# Visualizer_Bar.net
KiCad netlist of a schematic drawn in EAGLE
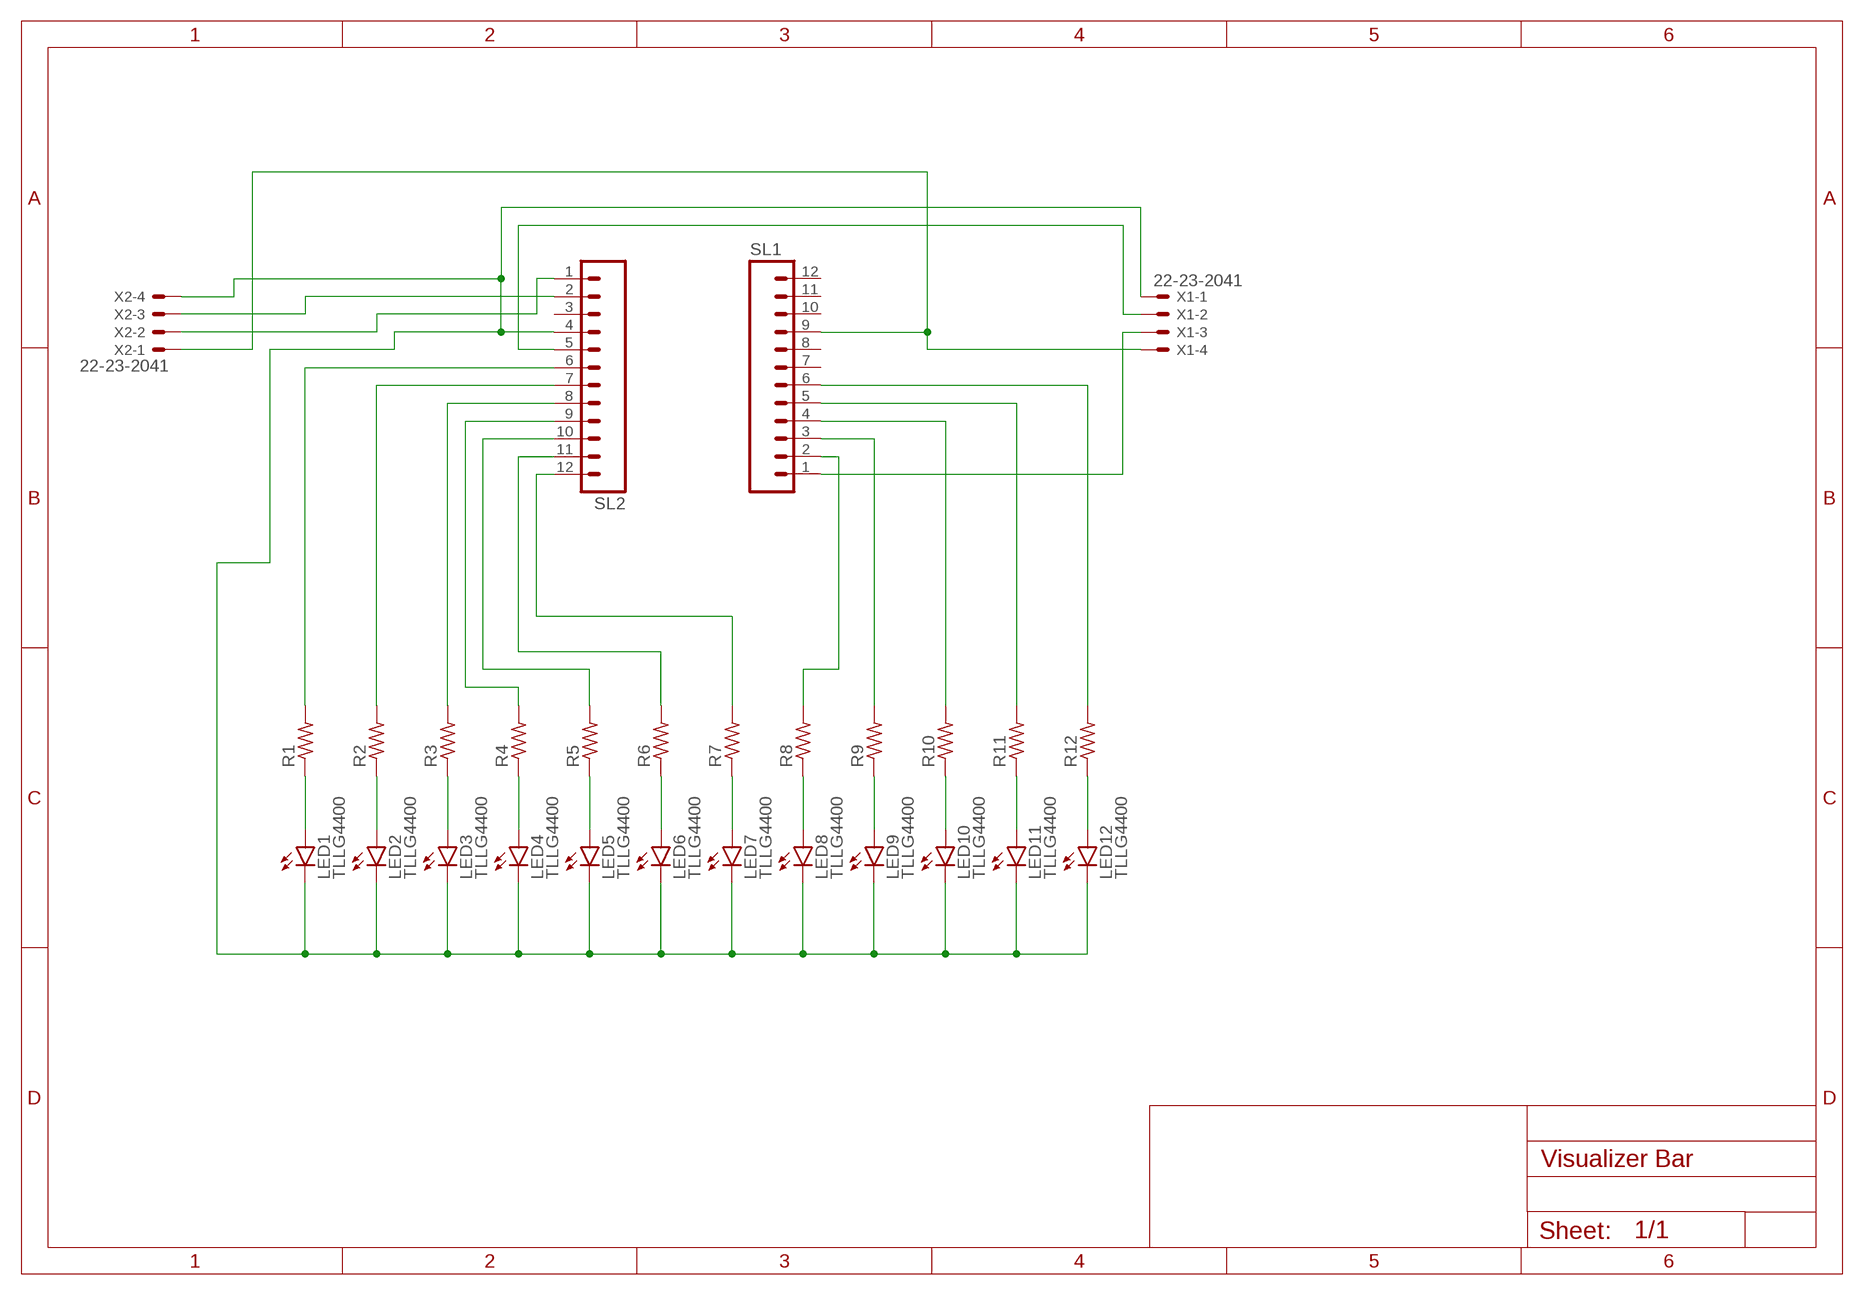
[diagram p0: schematic, sheet 1]

(export (version "E")
  (design (tool "Eeschema 10.0.6"))
  (components
    (comp (ref "LED1")
      (value "TLLG4400")
      (footprint "eagle-import:LED3MM")
      (fields (field (name "MF") "VISHAY SEMICONDUCTOR"))
      (libsource (lib "eagle-import") (part "TLLG4400"))
    )
    (comp (ref "LED2")
      (value "TLLG4400")
      (footprint "eagle-import:LED3MM")
      (fields (field (name "MF") "VISHAY SEMICONDUCTOR"))
      (libsource (lib "eagle-import") (part "TLLG4400"))
    )
    (comp (ref "LED3")
      (value "TLLG4400")
      (footprint "eagle-import:LED3MM")
      (fields (field (name "MF") "VISHAY SEMICONDUCTOR"))
      (libsource (lib "eagle-import") (part "TLLG4400"))
    )
    (comp (ref "LED4")
      (value "TLLG4400")
      (footprint "eagle-import:LED3MM")
      (fields (field (name "MF") "VISHAY SEMICONDUCTOR"))
      (libsource (lib "eagle-import") (part "TLLG4400"))
    )
    (comp (ref "LED5")
      (value "TLLG4400")
      (footprint "eagle-import:LED3MM")
      (fields (field (name "MF") "VISHAY SEMICONDUCTOR"))
      (libsource (lib "eagle-import") (part "TLLG4400"))
    )
    (comp (ref "LED6")
      (value "TLLG4400")
      (footprint "eagle-import:LED3MM")
      (fields (field (name "MF") "VISHAY SEMICONDUCTOR"))
      (libsource (lib "eagle-import") (part "TLLG4400"))
    )
    (comp (ref "LED7")
      (value "TLLG4400")
      (footprint "eagle-import:LED3MM")
      (fields (field (name "MF") "VISHAY SEMICONDUCTOR"))
      (libsource (lib "eagle-import") (part "TLLG4400"))
    )
    (comp (ref "LED8")
      (value "TLLG4400")
      (footprint "eagle-import:LED3MM")
      (fields (field (name "MF") "VISHAY SEMICONDUCTOR"))
      (libsource (lib "eagle-import") (part "TLLG4400"))
    )
    (comp (ref "LED9")
      (value "TLLG4400")
      (footprint "eagle-import:LED3MM")
      (fields (field (name "MF") "VISHAY SEMICONDUCTOR"))
      (libsource (lib "eagle-import") (part "TLLG4400"))
    )
    (comp (ref "LED10")
      (value "TLLG4400")
      (footprint "eagle-import:LED3MM")
      (fields (field (name "MF") "VISHAY SEMICONDUCTOR"))
      (libsource (lib "eagle-import") (part "TLLG4400"))
    )
    (comp (ref "LED11")
      (value "TLLG4400")
      (footprint "eagle-import:LED3MM")
      (fields (field (name "MF") "VISHAY SEMICONDUCTOR"))
      (libsource (lib "eagle-import") (part "TLLG4400"))
    )
    (comp (ref "LED12")
      (value "TLLG4400")
      (footprint "eagle-import:LED3MM")
      (fields (field (name "MF") "VISHAY SEMICONDUCTOR"))
      (libsource (lib "eagle-import") (part "TLLG4400"))
    )
    (comp (ref "R1")
      (value "R-US_0204/5")
      (footprint "eagle-import:0204_5")
      (libsource (lib "eagle-import") (part "R-US_0204/5"))
    )
    (comp (ref "R2")
      (value "R-US_0204/5")
      (footprint "eagle-import:0204_5")
      (libsource (lib "eagle-import") (part "R-US_0204/5"))
    )
    (comp (ref "R3")
      (value "R-US_0204/5")
      (footprint "eagle-import:0204_5")
      (libsource (lib "eagle-import") (part "R-US_0204/5"))
    )
    (comp (ref "R4")
      (value "R-US_0204/5")
      (footprint "eagle-import:0204_5")
      (libsource (lib "eagle-import") (part "R-US_0204/5"))
    )
    (comp (ref "R5")
      (value "R-US_0204/5")
      (footprint "eagle-import:0204_5")
      (libsource (lib "eagle-import") (part "R-US_0204/5"))
    )
    (comp (ref "R6")
      (value "R-US_0204/5")
      (footprint "eagle-import:0204_5")
      (libsource (lib "eagle-import") (part "R-US_0204/5"))
    )
    (comp (ref "R7")
      (value "R-US_0204/5")
      (footprint "eagle-import:0204_5")
      (libsource (lib "eagle-import") (part "R-US_0204/5"))
    )
    (comp (ref "R8")
      (value "R-US_0204/5")
      (footprint "eagle-import:0204_5")
      (libsource (lib "eagle-import") (part "R-US_0204/5"))
    )
    (comp (ref "R9")
      (value "R-US_0204/5")
      (footprint "eagle-import:0204_5")
      (libsource (lib "eagle-import") (part "R-US_0204/5"))
    )
    (comp (ref "R10")
      (value "R-US_0204/5")
      (footprint "eagle-import:0204_5")
      (libsource (lib "eagle-import") (part "R-US_0204/5"))
    )
    (comp (ref "R11")
      (value "R-US_0204/5")
      (footprint "eagle-import:0204_5")
      (libsource (lib "eagle-import") (part "R-US_0204/5"))
    )
    (comp (ref "R12")
      (value "R-US_0204/5")
      (footprint "eagle-import:0204_5")
      (libsource (lib "eagle-import") (part "R-US_0204/5"))
    )
    (comp (ref "SL1")
      (value "M12")
      (footprint "eagle-import:12P")
      (libsource (lib "eagle-import") (part "M12"))
    )
    (comp (ref "SL2")
      (value "M12")
      (footprint "eagle-import:12P")
      (libsource (lib "eagle-import") (part "M12"))
    )
    (comp (ref "X1")
      (value "22-23-2041")
      (footprint "eagle-import:22-23-2041")
      (fields (field (name "MF") "MOLEX"))
      (libsource (lib "eagle-import") (part "22-23-2041"))
    )
    (comp (ref "X2")
      (value "22-23-2041")
      (footprint "eagle-import:22-23-2041")
      (fields (field (name "MF") "MOLEX"))
      (libsource (lib "eagle-import") (part "22-23-2041"))
    )
  )
  (nets
    (net (code "1") (name "Net-(LED1-C)") (class "Default")
      (node (ref "LED1") (pin "K") (pinfunction "C_K") (pintype "passive"))
      (node (ref "LED10") (pin "K") (pinfunction "C_K") (pintype "passive"))
      (node (ref "LED11") (pin "K") (pinfunction "C_K") (pintype "passive"))
      (node (ref "LED12") (pin "K") (pinfunction "C_K") (pintype "passive"))
      (node (ref "LED2") (pin "K") (pinfunction "C_K") (pintype "passive"))
      (node (ref "LED3") (pin "K") (pinfunction "C_K") (pintype "passive"))
      (node (ref "LED4") (pin "K") (pinfunction "C_K") (pintype "passive"))
      (node (ref "LED5") (pin "K") (pinfunction "C_K") (pintype "passive"))
      (node (ref "LED6") (pin "K") (pinfunction "C_K") (pintype "passive"))
      (node (ref "LED7") (pin "K") (pinfunction "C_K") (pintype "passive"))
      (node (ref "LED8") (pin "K") (pinfunction "C_K") (pintype "passive"))
      (node (ref "LED9") (pin "K") (pinfunction "C_K") (pintype "passive"))
      (node (ref "SL2") (pin "4") (pinfunction "4_4") (pintype "passive"))
      (node (ref "X1") (pin "1") (pinfunction "S_1") (pintype "passive"))
      (node (ref "X2") (pin "4") (pinfunction "S_4") (pintype "passive"))
    )
    (net (code "2") (name "Net-(LED1-PadA)") (class "Default")
      (node (ref "LED1") (pin "A") (pinfunction "A_A") (pintype "passive"))
      (node (ref "R1") (pin "1") (pinfunction "1_1") (pintype "passive"))
    )
    (net (code "3") (name "Net-(LED2-PadA)") (class "Default")
      (node (ref "LED2") (pin "A") (pinfunction "A_A") (pintype "passive"))
      (node (ref "R2") (pin "1") (pinfunction "1_1") (pintype "passive"))
    )
    (net (code "4") (name "Net-(LED3-PadA)") (class "Default")
      (node (ref "LED3") (pin "A") (pinfunction "A_A") (pintype "passive"))
      (node (ref "R3") (pin "1") (pinfunction "1_1") (pintype "passive"))
    )
    (net (code "5") (name "Net-(LED4-PadA)") (class "Default")
      (node (ref "LED4") (pin "A") (pinfunction "A_A") (pintype "passive"))
      (node (ref "R4") (pin "1") (pinfunction "1_1") (pintype "passive"))
    )
    (net (code "6") (name "Net-(LED5-PadA)") (class "Default")
      (node (ref "LED5") (pin "A") (pinfunction "A_A") (pintype "passive"))
      (node (ref "R5") (pin "1") (pinfunction "1_1") (pintype "passive"))
    )
    (net (code "7") (name "Net-(LED6-PadA)") (class "Default")
      (node (ref "LED6") (pin "A") (pinfunction "A_A") (pintype "passive"))
      (node (ref "R6") (pin "1") (pinfunction "1_1") (pintype "passive"))
    )
    (net (code "8") (name "Net-(LED7-PadA)") (class "Default")
      (node (ref "LED7") (pin "A") (pinfunction "A_A") (pintype "passive"))
      (node (ref "R7") (pin "1") (pinfunction "1_1") (pintype "passive"))
    )
    (net (code "9") (name "Net-(LED8-PadA)") (class "Default")
      (node (ref "LED8") (pin "A") (pinfunction "A_A") (pintype "passive"))
      (node (ref "R8") (pin "1") (pinfunction "1_1") (pintype "passive"))
    )
    (net (code "10") (name "Net-(LED9-PadA)") (class "Default")
      (node (ref "LED9") (pin "A") (pinfunction "A_A") (pintype "passive"))
      (node (ref "R9") (pin "1") (pinfunction "1_1") (pintype "passive"))
    )
    (net (code "11") (name "Net-(LED10-PadA)") (class "Default")
      (node (ref "LED10") (pin "A") (pinfunction "A_A") (pintype "passive"))
      (node (ref "R10") (pin "1") (pinfunction "1_1") (pintype "passive"))
    )
    (net (code "12") (name "Net-(LED11-PadA)") (class "Default")
      (node (ref "LED11") (pin "A") (pinfunction "A_A") (pintype "passive"))
      (node (ref "R11") (pin "1") (pinfunction "1_1") (pintype "passive"))
    )
    (net (code "13") (name "Net-(LED12-PadA)") (class "Default")
      (node (ref "LED12") (pin "A") (pinfunction "A_A") (pintype "passive"))
      (node (ref "R12") (pin "1") (pinfunction "1_1") (pintype "passive"))
    )
    (net (code "14") (name "Net-(R1-Pad2)") (class "Default")
      (node (ref "R1") (pin "2") (pinfunction "2_2") (pintype "passive"))
      (node (ref "SL2") (pin "6") (pinfunction "6_6") (pintype "passive"))
    )
    (net (code "15") (name "Net-(R2-Pad2)") (class "Default")
      (node (ref "R2") (pin "2") (pinfunction "2_2") (pintype "passive"))
      (node (ref "SL2") (pin "7") (pinfunction "7_7") (pintype "passive"))
    )
    (net (code "16") (name "Net-(R3-Pad2)") (class "Default")
      (node (ref "R3") (pin "2") (pinfunction "2_2") (pintype "passive"))
      (node (ref "SL2") (pin "8") (pinfunction "8_8") (pintype "passive"))
    )
    (net (code "17") (name "Net-(R4-Pad2)") (class "Default")
      (node (ref "R4") (pin "2") (pinfunction "2_2") (pintype "passive"))
      (node (ref "SL2") (pin "9") (pinfunction "9_9") (pintype "passive"))
    )
    (net (code "18") (name "Net-(R5-Pad2)") (class "Default")
      (node (ref "R5") (pin "2") (pinfunction "2_2") (pintype "passive"))
      (node (ref "SL2") (pin "10") (pinfunction "10_10") (pintype "passive"))
    )
    (net (code "19") (name "Net-(R6-Pad2)") (class "Default")
      (node (ref "R6") (pin "2") (pinfunction "2_2") (pintype "passive"))
      (node (ref "SL2") (pin "11") (pinfunction "11_11") (pintype "passive"))
    )
    (net (code "20") (name "Net-(R7-Pad2)") (class "Default")
      (node (ref "R7") (pin "2") (pinfunction "2_2") (pintype "passive"))
      (node (ref "SL2") (pin "12") (pinfunction "12_12") (pintype "passive"))
    )
    (net (code "21") (name "Net-(R8-Pad2)") (class "Default")
      (node (ref "R8") (pin "2") (pinfunction "2_2") (pintype "passive"))
      (node (ref "SL1") (pin "2") (pinfunction "2_2") (pintype "passive"))
    )
    (net (code "22") (name "Net-(R9-Pad2)") (class "Default")
      (node (ref "R9") (pin "2") (pinfunction "2_2") (pintype "passive"))
      (node (ref "SL1") (pin "3") (pinfunction "3_3") (pintype "passive"))
    )
    (net (code "23") (name "Net-(R10-Pad2)") (class "Default")
      (node (ref "R10") (pin "2") (pinfunction "2_2") (pintype "passive"))
      (node (ref "SL1") (pin "4") (pinfunction "4_4") (pintype "passive"))
    )
    (net (code "24") (name "Net-(R11-Pad2)") (class "Default")
      (node (ref "R11") (pin "2") (pinfunction "2_2") (pintype "passive"))
      (node (ref "SL1") (pin "5") (pinfunction "5_5") (pintype "passive"))
    )
    (net (code "25") (name "Net-(R12-Pad2)") (class "Default")
      (node (ref "R12") (pin "2") (pinfunction "2_2") (pintype "passive"))
      (node (ref "SL1") (pin "6") (pinfunction "6_6") (pintype "passive"))
    )
    (net (code "26") (name "Net-(X1B-S)") (class "Default")
      (node (ref "SL2") (pin "5") (pinfunction "5_5") (pintype "passive"))
      (node (ref "X1") (pin "2") (pinfunction "S_2") (pintype "passive"))
    )
    (net (code "27") (name "Net-(X1C-S)") (class "Default")
      (node (ref "SL1") (pin "1") (pinfunction "1_1") (pintype "passive"))
      (node (ref "X1") (pin "3") (pinfunction "S_3") (pintype "passive"))
    )
    (net (code "28") (name "Net-(X1D-S)") (class "Default")
      (node (ref "SL1") (pin "9") (pinfunction "9_9") (pintype "passive"))
      (node (ref "X1") (pin "4") (pinfunction "S_4") (pintype "passive"))
      (node (ref "X2") (pin "1") (pinfunction "S_1") (pintype "passive"))
    )
    (net (code "29") (name "Net-(X2B-S)") (class "Default")
      (node (ref "SL2") (pin "1") (pinfunction "1_1") (pintype "passive"))
      (node (ref "X2") (pin "2") (pinfunction "S_2") (pintype "passive"))
    )
    (net (code "30") (name "Net-(X2C-S)") (class "Default")
      (node (ref "SL2") (pin "2") (pinfunction "2_2") (pintype "passive"))
      (node (ref "X2") (pin "3") (pinfunction "S_3") (pintype "passive"))
    )
    (net (code "31") (name "unconnected-(SL1-Pad7)") (class "Default")
      (node (ref "SL1") (pin "7") (pinfunction "7_7") (pintype "passive"))
    )
    (net (code "32") (name "unconnected-(SL1-Pad8)") (class "Default")
      (node (ref "SL1") (pin "8") (pinfunction "8_8") (pintype "passive"))
    )
    (net (code "33") (name "unconnected-(SL1-Pad10)") (class "Default")
      (node (ref "SL1") (pin "10") (pinfunction "10_10") (pintype "passive"))
    )
    (net (code "34") (name "unconnected-(SL1-Pad11)") (class "Default")
      (node (ref "SL1") (pin "11") (pinfunction "11_11") (pintype "passive"))
    )
    (net (code "35") (name "unconnected-(SL1-Pad12)") (class "Default")
      (node (ref "SL1") (pin "12") (pinfunction "12_12") (pintype "passive"))
    )
    (net (code "36") (name "unconnected-(SL2-Pad3)") (class "Default")
      (node (ref "SL2") (pin "3") (pinfunction "3_3") (pintype "passive"))
    )
  )
)
